# C_376p667.net
KiCad netlist of a schematic drawn in Altium Designer
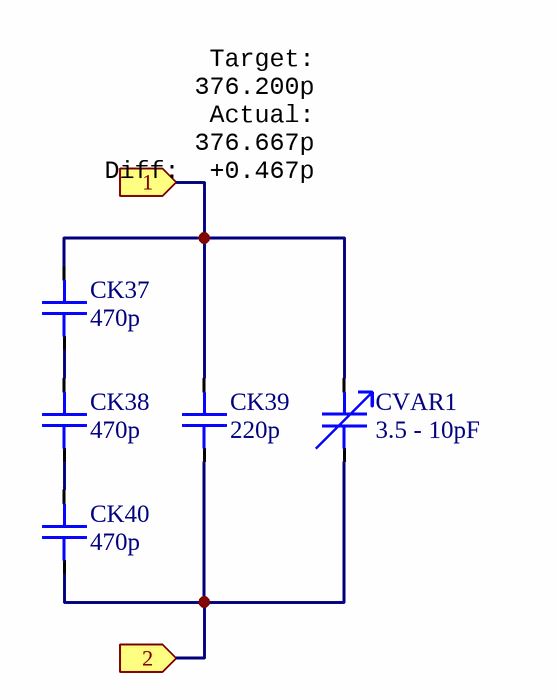
[diagram p0: C_376p667.SchDoc]

(export (version "E")
  (design (tool "Eeschema 10.0.6"))
  (components
    (comp (ref "CK37")
      (value "470p")
      (footprint "CAPC1005X06N(SMC0402)")
      (description "C; 470p; 50V; 1%; NP0/C0G; ??;")
      (fields (field (name "MANUFACTURER") "Kemet: C0402C471F5GAC7867;;Murata: GRM1555C1H471FA01D"))
      (libsource (lib "altium_sql") (part "CK"))
    )
    (comp (ref "CK38")
      (value "470p")
      (footprint "CAPC1005X06N(SMC0402)")
      (description "C; 470p; 50V; 1%; NP0/C0G; ??;")
      (fields (field (name "MANUFACTURER") "Kemet: C0402C471F5GAC7867;;Murata: GRM1555C1H471FA01D"))
      (libsource (lib "altium_sql") (part "CK"))
    )
    (comp (ref "CK39")
      (value "220p")
      (footprint "CAPC1005X06N(SMC0402)")
      (description "C; 220p; 50V; 1%; NP0/C0G; ??;")
      (fields (field (name "MANUFACTURER") "YAGEO: CC0402FRNPO9BN221"))
      (libsource (lib "altium_sql") (part "CK"))
    )
    (comp (ref "CK40")
      (value "470p")
      (footprint "CAPC1005X06N(SMC0402)")
      (description "C; 470p; 50V; 1%; NP0/C0G; ??;")
      (fields (field (name "MANUFACTURER") "Kemet: C0402C471F5GAC7867;;Murata: GRM1555C1H471FA01D"))
      (libsource (lib "altium_sql") (part "CK"))
    )
    (comp (ref "CVAR1")
      (value "3.5 - 10pF")
      (footprint "CTSC3S")
      (description "3.5 - 10pF, 50V")
      (libsource (lib "custom-footprints") (part "CTSC3S"))
    )
  )
  (nets
    (net (code "1") (name "/1") (class "Default")
      (node (ref "CK37") (pin "1") (pinfunction "1_1") (pintype "passive"))
      (node (ref "CK39") (pin "1") (pinfunction "1_1") (pintype "passive"))
      (node (ref "CVAR1") (pin "1") (pinfunction "1_1") (pintype "passive"))
    )
    (net (code "2") (name "/2") (class "Default")
      (node (ref "CK39") (pin "2") (pinfunction "2_2") (pintype "passive"))
      (node (ref "CK40") (pin "2") (pinfunction "2_2") (pintype "passive"))
      (node (ref "CVAR1") (pin "2") (pinfunction "2_2") (pintype "passive"))
    )
    (net (code "3") (name "Net-(CK37-Pad2)") (class "Default")
      (node (ref "CK37") (pin "2") (pinfunction "2_2") (pintype "passive"))
      (node (ref "CK38") (pin "1") (pinfunction "1_1") (pintype "passive"))
    )
    (net (code "4") (name "Net-(CK38-Pad2)") (class "Default")
      (node (ref "CK38") (pin "2") (pinfunction "2_2") (pintype "passive"))
      (node (ref "CK40") (pin "1") (pinfunction "1_1") (pintype "passive"))
    )
  )
)
